# Channel_A.net
KiCad netlist of a schematic drawn in Altium Designer
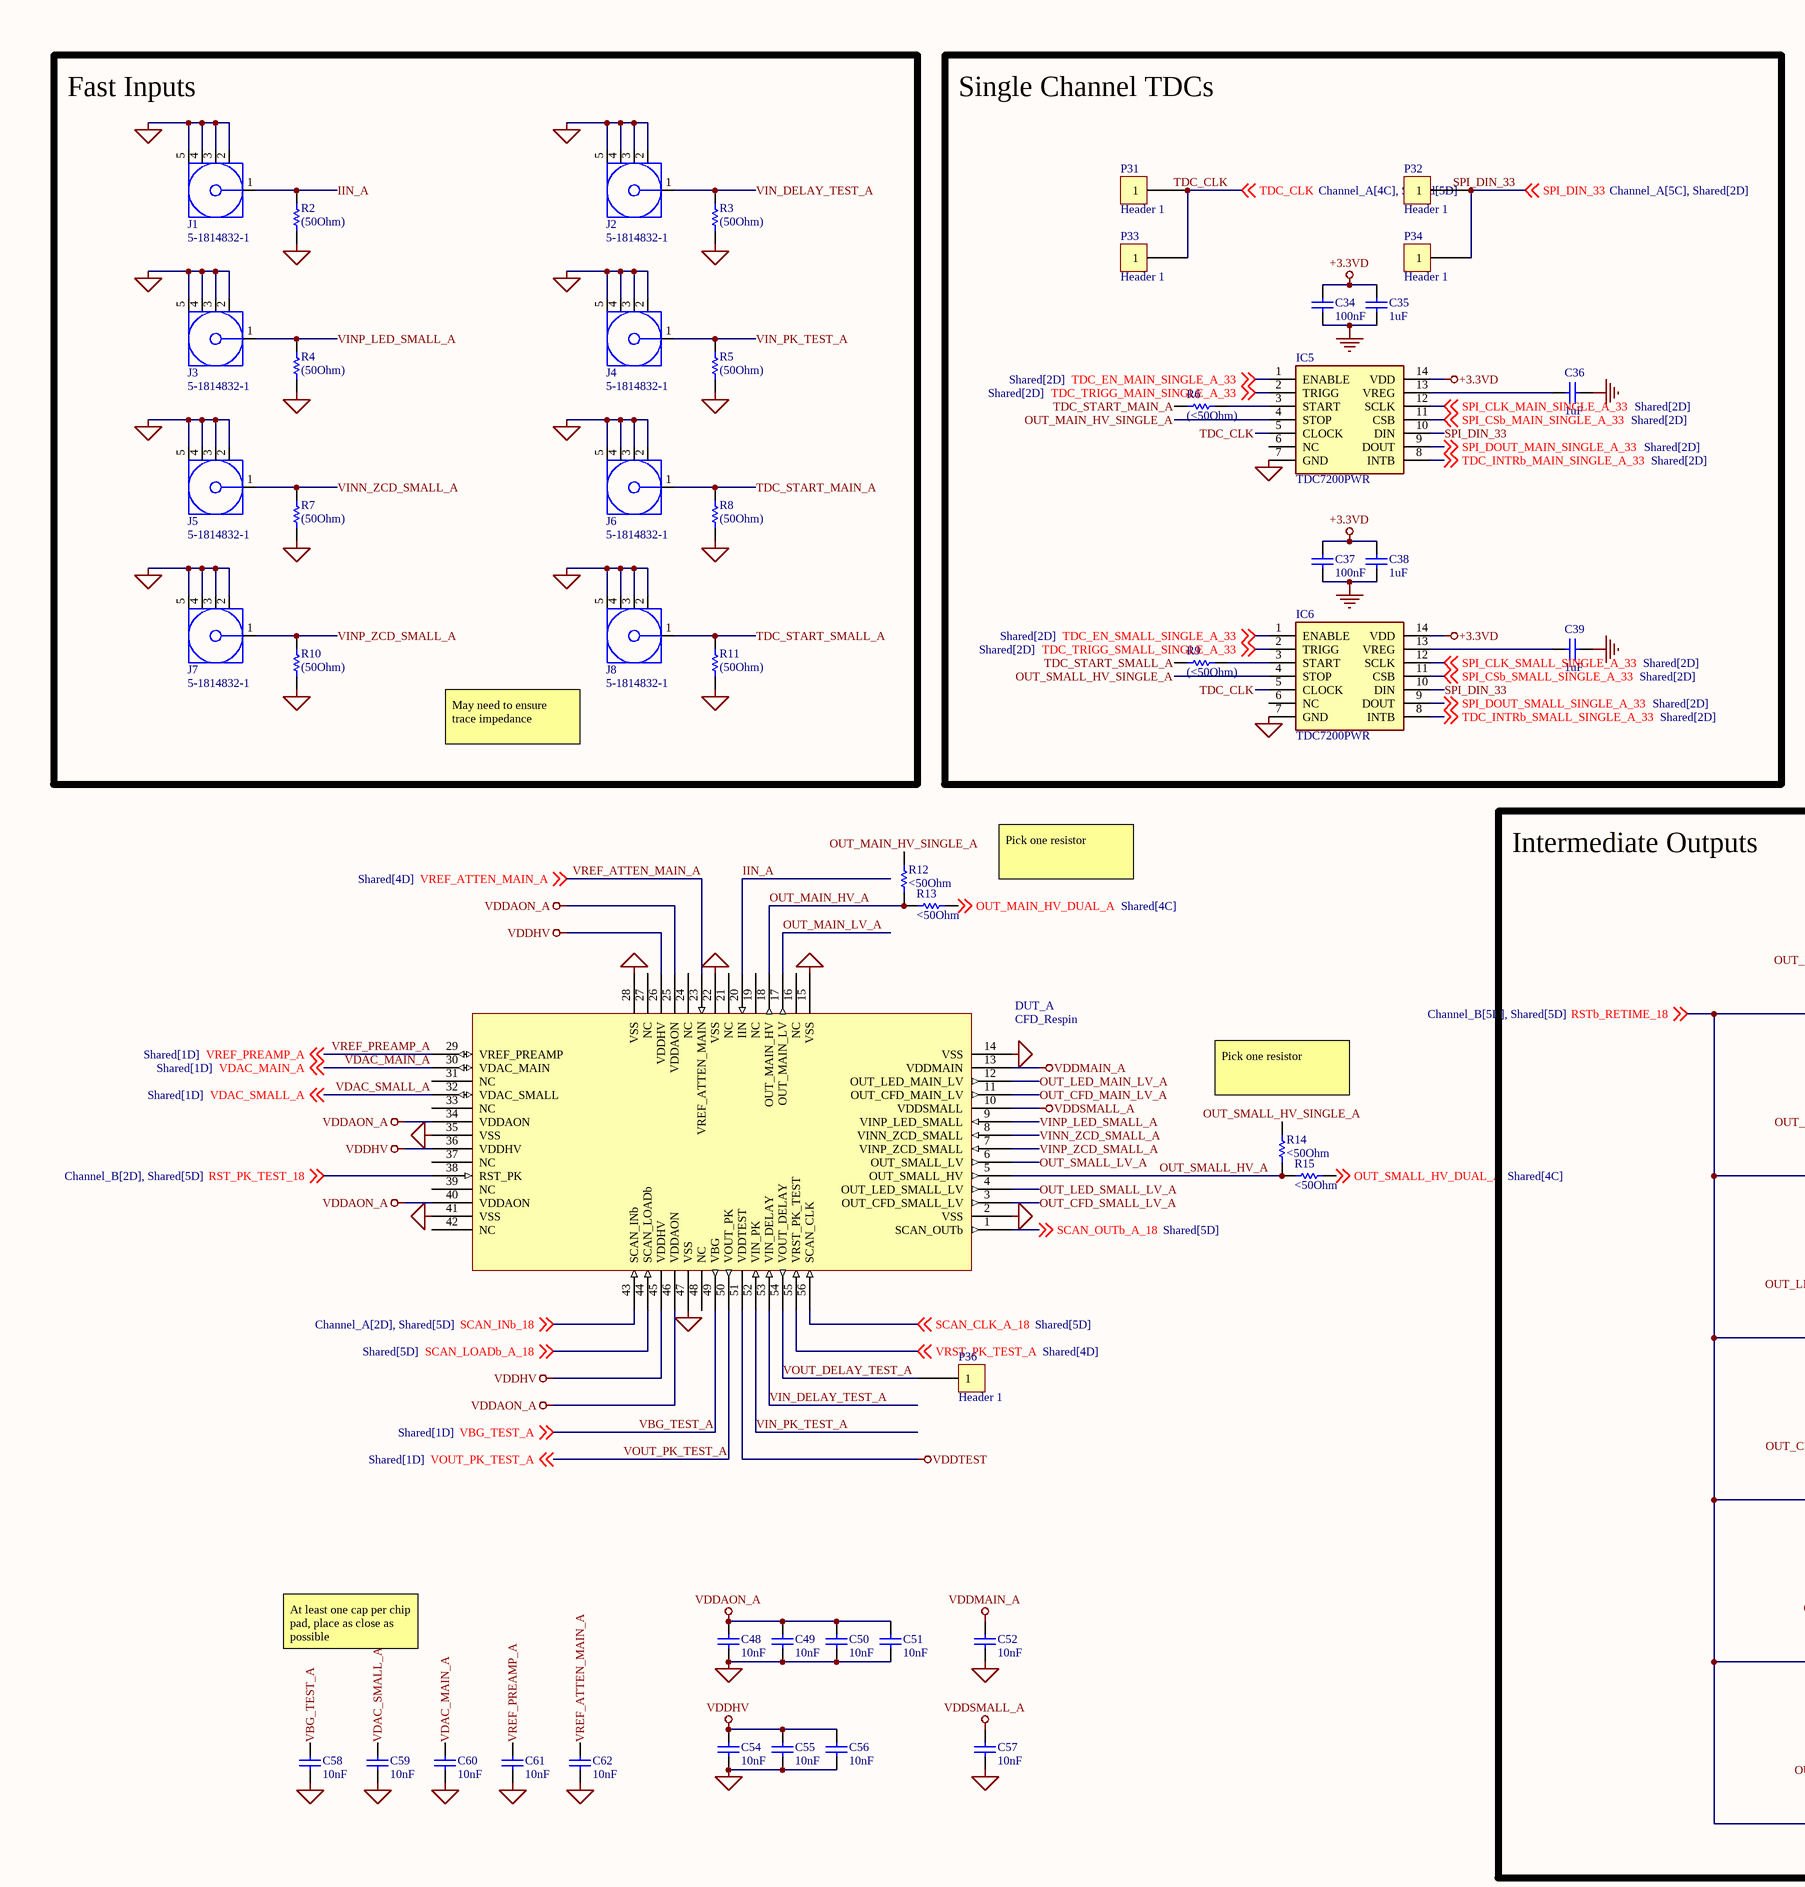
[diagram p0: Channel_A.SchDoc, left]
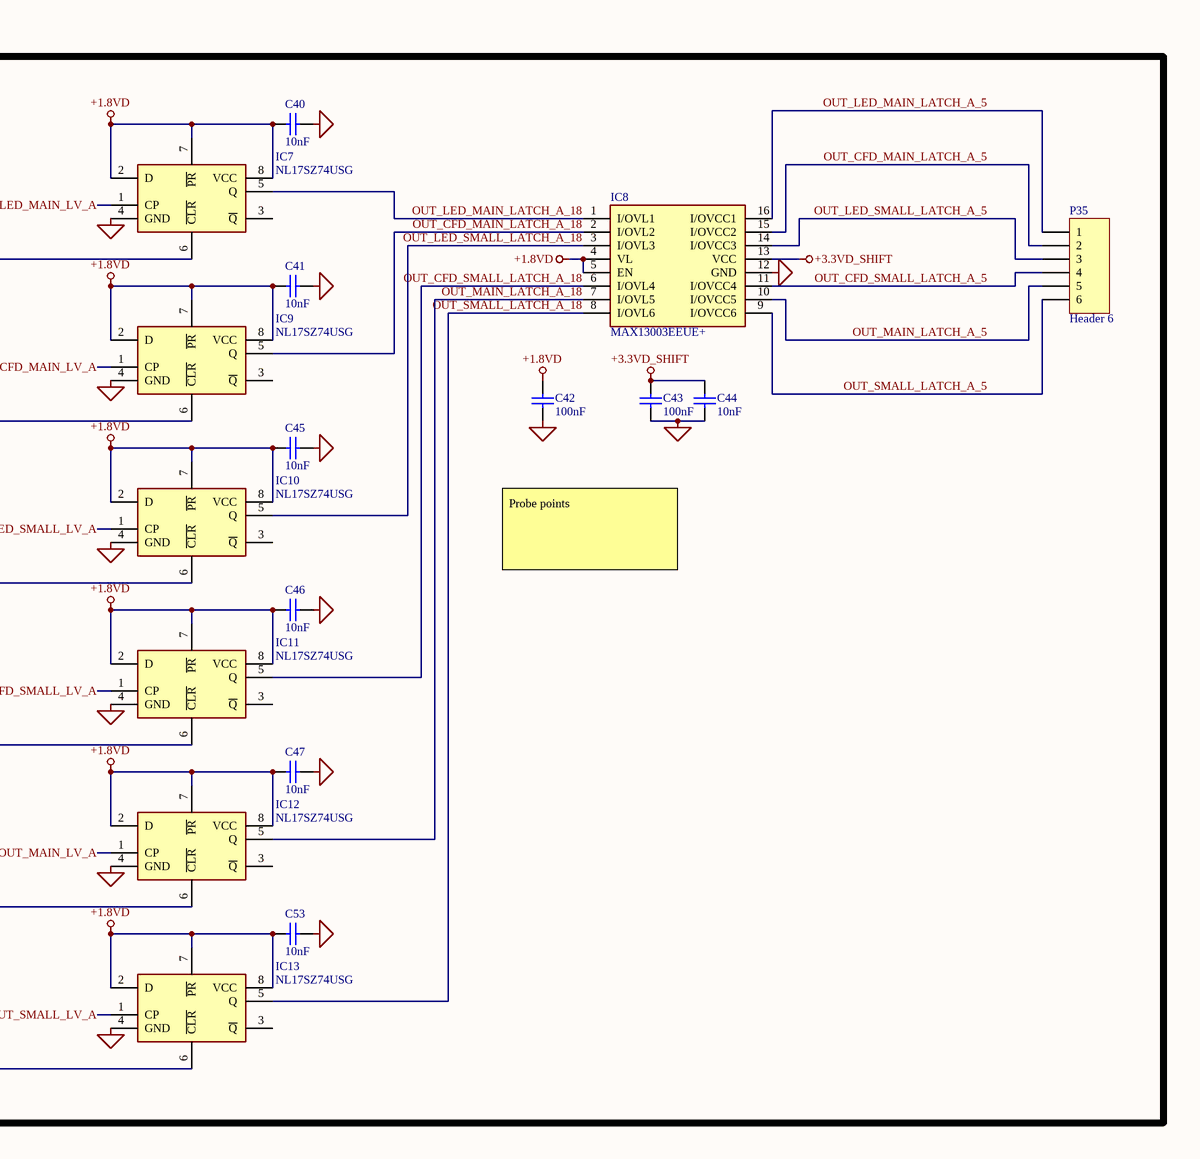
[diagram p1: Channel_A.SchDoc, right]

(export (version "E")
  (design (tool "Eeschema 10.0.6"))
  (components
    (comp (ref "C34")
      (value "100nF")
      (footprint "CAPC1608X90X35ML10T15")
      (description "0603")
      (fields (field (name "MANUFACTURER") "Murata"))
      (libsource (lib "Altium Content Vault") (part "CAP-NP-2"))
    )
    (comp (ref "C35")
      (value "1uF")
      (footprint "CAPC1608X90X35ML10T15")
      (description "0603")
      (fields (field (name "MANUFACTURER") "Murata"))
      (libsource (lib "Altium Content Vault") (part "CAP-NP-2"))
    )
    (comp (ref "C36")
      (value "1uF")
      (footprint "CAPC1608X90X35ML10T15")
      (description "0603")
      (fields (field (name "MANUFACTURER") "Murata"))
      (libsource (lib "Altium Content Vault") (part "CAP-NP-2"))
    )
    (comp (ref "C37")
      (value "100nF")
      (footprint "CAPC1608X90X35ML10T15")
      (description "0603")
      (fields (field (name "MANUFACTURER") "Murata"))
      (libsource (lib "Altium Content Vault") (part "CAP-NP-2"))
    )
    (comp (ref "C38")
      (value "1uF")
      (footprint "CAPC1608X90X35ML10T15")
      (description "0603")
      (fields (field (name "MANUFACTURER") "Murata"))
      (libsource (lib "Altium Content Vault") (part "CAP-NP-2"))
    )
    (comp (ref "C39")
      (value "1uF")
      (footprint "CAPC1608X90X35ML10T15")
      (description "0603")
      (fields (field (name "MANUFACTURER") "Murata"))
      (libsource (lib "Altium Content Vault") (part "CAP-NP-2"))
    )
    (comp (ref "C40")
      (value "10nF")
      (footprint "CAPC1608X90X35ML10T15")
      (description "0603")
      (fields (field (name "MANUFACTURER") "Murata"))
      (libsource (lib "Altium Content Vault") (part "CAP-NP-2"))
    )
    (comp (ref "C41")
      (value "10nF")
      (footprint "CAPC1608X90X35ML10T15")
      (description "0603")
      (fields (field (name "MANUFACTURER") "Murata"))
      (libsource (lib "Altium Content Vault") (part "CAP-NP-2"))
    )
    (comp (ref "C42")
      (value "100nF")
      (footprint "CAPC1608X90X35ML10T15")
      (description "0603")
      (fields (field (name "MANUFACTURER") "Murata"))
      (libsource (lib "Altium Content Vault") (part "CAP-NP-2"))
    )
    (comp (ref "C43")
      (value "100nF")
      (footprint "CAPC1608X90X35ML10T15")
      (description "0603")
      (fields (field (name "MANUFACTURER") "Murata"))
      (libsource (lib "Altium Content Vault") (part "CAP-NP-2"))
    )
    (comp (ref "C44")
      (value "10nF")
      (footprint "CAPC1608X90X35ML10T15")
      (description "0603")
      (fields (field (name "MANUFACTURER") "Murata"))
      (libsource (lib "Altium Content Vault") (part "CAP-NP-2"))
    )
    (comp (ref "C45")
      (value "10nF")
      (footprint "CAPC1608X90X35ML10T15")
      (description "0603")
      (fields (field (name "MANUFACTURER") "Murata"))
      (libsource (lib "Altium Content Vault") (part "CAP-NP-2"))
    )
    (comp (ref "C46")
      (value "10nF")
      (footprint "CAPC1608X90X35ML10T15")
      (description "0603")
      (fields (field (name "MANUFACTURER") "Murata"))
      (libsource (lib "Altium Content Vault") (part "CAP-NP-2"))
    )
    (comp (ref "C47")
      (value "10nF")
      (footprint "CAPC1608X90X35ML10T15")
      (description "0603")
      (fields (field (name "MANUFACTURER") "Murata"))
      (libsource (lib "Altium Content Vault") (part "CAP-NP-2"))
    )
    (comp (ref "C48")
      (value "10nF")
      (footprint "CAPC1608X90X35ML10T15")
      (description "0603")
      (fields (field (name "MANUFACTURER") "Murata"))
      (libsource (lib "Altium Content Vault") (part "CAP-NP-2"))
    )
    (comp (ref "C49")
      (value "10nF")
      (footprint "CAPC1608X90X35ML10T15")
      (description "0603")
      (fields (field (name "MANUFACTURER") "Murata"))
      (libsource (lib "Altium Content Vault") (part "CAP-NP-2"))
    )
    (comp (ref "C50")
      (value "10nF")
      (footprint "CAPC1608X90X35ML10T15")
      (description "0603")
      (fields (field (name "MANUFACTURER") "Murata"))
      (libsource (lib "Altium Content Vault") (part "CAP-NP-2"))
    )
    (comp (ref "C51")
      (value "10nF")
      (footprint "CAPC1608X90X35ML10T15")
      (description "0603")
      (fields (field (name "MANUFACTURER") "Murata"))
      (libsource (lib "Altium Content Vault") (part "CAP-NP-2"))
    )
    (comp (ref "C52")
      (value "10nF")
      (footprint "CAPC1608X90X35ML10T15")
      (description "0603")
      (fields (field (name "MANUFACTURER") "Murata"))
      (libsource (lib "Altium Content Vault") (part "CAP-NP-2"))
    )
    (comp (ref "C53")
      (value "10nF")
      (footprint "CAPC1608X90X35ML10T15")
      (description "0603")
      (fields (field (name "MANUFACTURER") "Murata"))
      (libsource (lib "Altium Content Vault") (part "CAP-NP-2"))
    )
    (comp (ref "C54")
      (value "10nF")
      (footprint "CAPC1608X90X35ML10T15")
      (description "0603")
      (fields (field (name "MANUFACTURER") "Murata"))
      (libsource (lib "Altium Content Vault") (part "CAP-NP-2"))
    )
    (comp (ref "C55")
      (value "10nF")
      (footprint "CAPC1608X90X35ML10T15")
      (description "0603")
      (fields (field (name "MANUFACTURER") "Murata"))
      (libsource (lib "Altium Content Vault") (part "CAP-NP-2"))
    )
    (comp (ref "C56")
      (value "10nF")
      (footprint "CAPC1608X90X35ML10T15")
      (description "0603")
      (fields (field (name "MANUFACTURER") "Murata"))
      (libsource (lib "Altium Content Vault") (part "CAP-NP-2"))
    )
    (comp (ref "C57")
      (value "10nF")
      (footprint "CAPC1608X90X35ML10T15")
      (description "0603")
      (fields (field (name "MANUFACTURER") "Murata"))
      (libsource (lib "Altium Content Vault") (part "CAP-NP-2"))
    )
    (comp (ref "C58")
      (value "10nF")
      (footprint "CAPC1608X90X35ML10T15")
      (description "0603")
      (fields (field (name "MANUFACTURER") "Murata"))
      (libsource (lib "Altium Content Vault") (part "CAP-NP-2"))
    )
    (comp (ref "C59")
      (value "10nF")
      (footprint "CAPC1608X90X35ML10T15")
      (description "0603")
      (fields (field (name "MANUFACTURER") "Murata"))
      (libsource (lib "Altium Content Vault") (part "CAP-NP-2"))
    )
    (comp (ref "C60")
      (value "10nF")
      (footprint "CAPC1608X90X35ML10T15")
      (description "0603")
      (fields (field (name "MANUFACTURER") "Murata"))
      (libsource (lib "Altium Content Vault") (part "CAP-NP-2"))
    )
    (comp (ref "C61")
      (value "10nF")
      (footprint "CAPC1608X90X35ML10T15")
      (description "0603")
      (fields (field (name "MANUFACTURER") "Murata"))
      (libsource (lib "Altium Content Vault") (part "CAP-NP-2"))
    )
    (comp (ref "C62")
      (value "10nF")
      (footprint "CAPC1608X90X35ML10T15")
      (description "0603")
      (fields (field (name "MANUFACTURER") "Murata"))
      (libsource (lib "Altium Content Vault") (part "CAP-NP-2"))
    )
    (comp (ref "DUT_A")
      (value "CFD_Respin")
      (footprint "QFN50P800X800X80_HS-57N_WIDEVIAS")
      (libsource (lib "intlib") (part "CFD_Respin"))
    )
    (comp (ref "IC5")
      (value "TDC7200PWR")
      (footprint "SamacSys:SOP65P640X120-14N")
      (description "Integrated Circuit")
      (libsource (lib "*") (part "TDC7200PWR"))
    )
    (comp (ref "IC6")
      (value "TDC7200PWR")
      (footprint "SamacSys:SOP65P640X120-14N")
      (description "Integrated Circuit")
      (libsource (lib "*") (part "TDC7200PWR"))
    )
    (comp (ref "IC7")
      (value "NL17SZ74USG")
      (footprint "SamacSys:SOP50P310X90-8N")
      (description "Flip Flops 1.65-5.5V CMOS Single D-Type")
      (libsource (lib "SamacSys") (part "NL17SZ74USG"))
    )
    (comp (ref "IC8")
      (value "MAX13003EEUE+")
      (footprint "SamacSys:SOP65P640X110-16N")
      (description "Integrated Circuit")
      (libsource (lib "*") (part "MAX13003EEUE+"))
    )
    (comp (ref "IC9")
      (value "NL17SZ74USG")
      (footprint "SamacSys:SOP50P310X90-8N")
      (description "Flip Flops 1.65-5.5V CMOS Single D-Type")
      (libsource (lib "SamacSys") (part "NL17SZ74USG"))
    )
    (comp (ref "IC10")
      (value "NL17SZ74USG")
      (footprint "SamacSys:SOP50P310X90-8N")
      (description "Flip Flops 1.65-5.5V CMOS Single D-Type")
      (libsource (lib "SamacSys") (part "NL17SZ74USG"))
    )
    (comp (ref "IC11")
      (value "NL17SZ74USG")
      (footprint "SamacSys:SOP50P310X90-8N")
      (description "Flip Flops 1.65-5.5V CMOS Single D-Type")
      (libsource (lib "SamacSys") (part "NL17SZ74USG"))
    )
    (comp (ref "IC12")
      (value "NL17SZ74USG")
      (footprint "SamacSys:SOP50P310X90-8N")
      (description "Flip Flops 1.65-5.5V CMOS Single D-Type")
      (libsource (lib "SamacSys") (part "NL17SZ74USG"))
    )
    (comp (ref "IC13")
      (value "NL17SZ74USG")
      (footprint "SamacSys:SOP50P310X90-8N")
      (description "Flip Flops 1.65-5.5V CMOS Single D-Type")
      (libsource (lib "SamacSys") (part "NL17SZ74USG"))
    )
    (comp (ref "J1")
      (value "5-1814832-1")
      (footprint "TECO-5-1814832-1_V")
      (fields (field (name "MANUFACTURER") "TE Connectivity"))
      (libsource (lib "Altium Content Vault") (part "CN-S-4F-RF5"))
    )
    (comp (ref "J2")
      (value "5-1814832-1")
      (footprint "TECO-5-1814832-1_V")
      (fields (field (name "MANUFACTURER") "TE Connectivity"))
      (libsource (lib "Altium Content Vault") (part "CN-S-4F-RF5"))
    )
    (comp (ref "J3")
      (value "5-1814832-1")
      (footprint "TECO-5-1814832-1_V")
      (fields (field (name "MANUFACTURER") "TE Connectivity"))
      (libsource (lib "Altium Content Vault") (part "CN-S-4F-RF5"))
    )
    (comp (ref "J4")
      (value "5-1814832-1")
      (footprint "TECO-5-1814832-1_V")
      (fields (field (name "MANUFACTURER") "TE Connectivity"))
      (libsource (lib "Altium Content Vault") (part "CN-S-4F-RF5"))
    )
    (comp (ref "J5")
      (value "5-1814832-1")
      (footprint "TECO-5-1814832-1_V")
      (fields (field (name "MANUFACTURER") "TE Connectivity"))
      (libsource (lib "Altium Content Vault") (part "CN-S-4F-RF5"))
    )
    (comp (ref "J6")
      (value "5-1814832-1")
      (footprint "TECO-5-1814832-1_V")
      (fields (field (name "MANUFACTURER") "TE Connectivity"))
      (libsource (lib "Altium Content Vault") (part "CN-S-4F-RF5"))
    )
    (comp (ref "J7")
      (value "5-1814832-1")
      (footprint "TECO-5-1814832-1_V")
      (fields (field (name "MANUFACTURER") "TE Connectivity"))
      (libsource (lib "Altium Content Vault") (part "CN-S-4F-RF5"))
    )
    (comp (ref "J8")
      (value "5-1814832-1")
      (footprint "TECO-5-1814832-1_V")
      (fields (field (name "MANUFACTURER") "TE Connectivity"))
      (libsource (lib "Altium Content Vault") (part "CN-S-4F-RF5"))
    )
    (comp (ref "P31") (value "Header 1") (footprint "Header1") (libsource (lib "intlib") (part "Header 1")))
    (comp (ref "P32") (value "Header 1") (footprint "Header1") (libsource (lib "intlib") (part "Header 1")))
    (comp (ref "P33") (value "Header 1") (footprint "Header1") (libsource (lib "intlib") (part "Header 1")))
    (comp (ref "P34") (value "Header 1") (footprint "Header1") (libsource (lib "intlib") (part "Header 1")))
    (comp (ref "P35")
      (value "Header 6")
      (footprint "HDR1X6")
      (description "Header, 6-Pin")
      (fields (field (name "PUBLISHER") "Altium Limited"))
      (libsource (lib "Miscellaneous Connectors") (part "Header 6"))
    )
    (comp (ref "P36") (value "Header 1") (footprint "Header1") (libsource (lib "") (part "Header 1_1")))
    (comp (ref "R2")
      (value "(50Ohm)")
      (footprint "RESC1609X50X30NL8T20")
      (description "0603")
      (fields (field (name "MANUFACTURER") "Vishay Semiconductor"))
      (libsource (lib "Altium Content Vault") (part "RES-2"))
    )
    (comp (ref "R3")
      (value "(50Ohm)")
      (footprint "RESC1609X50X30NL8T20")
      (description "0603")
      (fields (field (name "MANUFACTURER") "Vishay Semiconductor"))
      (libsource (lib "Altium Content Vault") (part "RES-2"))
    )
    (comp (ref "R4")
      (value "(50Ohm)")
      (footprint "RESC1609X50X30NL8T20")
      (description "0603")
      (fields (field (name "MANUFACTURER") "Vishay Semiconductor"))
      (libsource (lib "Altium Content Vault") (part "RES-2"))
    )
    (comp (ref "R5")
      (value "(50Ohm)")
      (footprint "RESC1609X50X30NL8T20")
      (description "0603")
      (fields (field (name "MANUFACTURER") "Vishay Semiconductor"))
      (libsource (lib "Altium Content Vault") (part "RES-2"))
    )
    (comp (ref "R6")
      (value "(<50Ohm)")
      (footprint "RESC1609X50X30NL8T20")
      (description "0603")
      (fields (field (name "MANUFACTURER") "Vishay Semiconductor"))
      (libsource (lib "Altium Content Vault") (part "RES-2"))
    )
    (comp (ref "R7")
      (value "(50Ohm)")
      (footprint "RESC1609X50X30NL8T20")
      (description "0603")
      (fields (field (name "MANUFACTURER") "Vishay Semiconductor"))
      (libsource (lib "Altium Content Vault") (part "RES-2"))
    )
    (comp (ref "R8")
      (value "(50Ohm)")
      (footprint "RESC1609X50X30NL8T20")
      (description "0603")
      (fields (field (name "MANUFACTURER") "Vishay Semiconductor"))
      (libsource (lib "Altium Content Vault") (part "RES-2"))
    )
    (comp (ref "R9")
      (value "(<50Ohm)")
      (footprint "RESC1609X50X30NL8T20")
      (description "0603")
      (fields (field (name "MANUFACTURER") "Vishay Semiconductor"))
      (libsource (lib "Altium Content Vault") (part "RES-2"))
    )
    (comp (ref "R10")
      (value "(50Ohm)")
      (footprint "RESC1609X50X30NL8T20")
      (description "0603")
      (fields (field (name "MANUFACTURER") "Vishay Semiconductor"))
      (libsource (lib "Altium Content Vault") (part "RES-2"))
    )
    (comp (ref "R11")
      (value "(50Ohm)")
      (footprint "RESC1609X50X30NL8T20")
      (description "0603")
      (fields (field (name "MANUFACTURER") "Vishay Semiconductor"))
      (libsource (lib "Altium Content Vault") (part "RES-2"))
    )
    (comp (ref "R12")
      (value "<50Ohm")
      (footprint "RESC1609X50X30NL8T20")
      (description "0603")
      (fields (field (name "MANUFACTURER") "Vishay Semiconductor"))
      (libsource (lib "Altium Content Vault") (part "RES-2"))
    )
    (comp (ref "R13")
      (value "<50Ohm")
      (footprint "RESC1609X50X30NL8T20")
      (description "0603")
      (fields (field (name "MANUFACTURER") "Vishay Semiconductor"))
      (libsource (lib "Altium Content Vault") (part "RES-2"))
    )
    (comp (ref "R14")
      (value "<50Ohm")
      (footprint "RESC1609X50X30NL8T20")
      (description "0603")
      (fields (field (name "MANUFACTURER") "Vishay Semiconductor"))
      (libsource (lib "Altium Content Vault") (part "RES-2"))
    )
    (comp (ref "R15")
      (value "<50Ohm")
      (footprint "RESC1609X50X30NL8T20")
      (description "0603")
      (fields (field (name "MANUFACTURER") "Vishay Semiconductor"))
      (libsource (lib "Altium Content Vault") (part "RES-2"))
    )
  )
  (nets
    (net (code "1") (name "+1.8VD") (class "Default")
      (node (ref "C40") (pin "2") (pinfunction "2_2") (pintype "passive"))
      (node (ref "C41") (pin "2") (pinfunction "2_2") (pintype "passive"))
      (node (ref "C42") (pin "2") (pinfunction "2_2") (pintype "passive"))
      (node (ref "C45") (pin "2") (pinfunction "2_2") (pintype "passive"))
      (node (ref "C46") (pin "2") (pinfunction "2_2") (pintype "passive"))
      (node (ref "C47") (pin "2") (pinfunction "2_2") (pintype "passive"))
      (node (ref "C53") (pin "2") (pinfunction "2_2") (pintype "passive"))
      (node (ref "IC10") (pin "2") (pinfunction "D_2") (pintype "passive"))
      (node (ref "IC10") (pin "7") (pinfunction "~{PR}_7") (pintype "passive"))
      (node (ref "IC10") (pin "8") (pinfunction "VCC_8") (pintype "passive"))
      (node (ref "IC11") (pin "2") (pinfunction "D_2") (pintype "passive"))
      (node (ref "IC11") (pin "7") (pinfunction "~{PR}_7") (pintype "passive"))
      (node (ref "IC11") (pin "8") (pinfunction "VCC_8") (pintype "passive"))
      (node (ref "IC12") (pin "2") (pinfunction "D_2") (pintype "passive"))
      (node (ref "IC12") (pin "7") (pinfunction "~{PR}_7") (pintype "passive"))
      (node (ref "IC12") (pin "8") (pinfunction "VCC_8") (pintype "passive"))
      (node (ref "IC13") (pin "2") (pinfunction "D_2") (pintype "passive"))
      (node (ref "IC13") (pin "7") (pinfunction "~{PR}_7") (pintype "passive"))
      (node (ref "IC13") (pin "8") (pinfunction "VCC_8") (pintype "passive"))
      (node (ref "IC7") (pin "2") (pinfunction "D_2") (pintype "passive"))
      (node (ref "IC7") (pin "7") (pinfunction "~{PR}_7") (pintype "passive"))
      (node (ref "IC7") (pin "8") (pinfunction "VCC_8") (pintype "passive"))
      (node (ref "IC8") (pin "4") (pinfunction "VL_4") (pintype "passive"))
      (node (ref "IC8") (pin "5") (pinfunction "EN_5") (pintype "passive"))
      (node (ref "IC9") (pin "2") (pinfunction "D_2") (pintype "passive"))
      (node (ref "IC9") (pin "7") (pinfunction "~{PR}_7") (pintype "passive"))
      (node (ref "IC9") (pin "8") (pinfunction "VCC_8") (pintype "passive"))
    )
    (net (code "2") (name "+3.3VD") (class "Default")
      (node (ref "C34") (pin "1") (pinfunction "1_1") (pintype "passive"))
      (node (ref "C35") (pin "1") (pinfunction "1_1") (pintype "passive"))
      (node (ref "C37") (pin "1") (pinfunction "1_1") (pintype "passive"))
      (node (ref "C38") (pin "1") (pinfunction "1_1") (pintype "passive"))
      (node (ref "IC5") (pin "14") (pinfunction "VDD_14") (pintype "passive"))
      (node (ref "IC6") (pin "14") (pinfunction "VDD_14") (pintype "passive"))
    )
    (net (code "3") (name "+3.3VD_SHIFT") (class "Default")
      (node (ref "C43") (pin "2") (pinfunction "2_2") (pintype "passive"))
      (node (ref "C44") (pin "2") (pinfunction "2_2") (pintype "passive"))
      (node (ref "IC8") (pin "13") (pinfunction "VCC_13") (pintype "passive"))
    )
    (net (code "4") (name "/IIN_A") (class "Default")
      (node (ref "DUT_A") (pin "20") (pinfunction "IIN_20") (pintype "input"))
      (node (ref "J1") (pin "1") (pinfunction "1_1") (pintype "passive"))
      (node (ref "R2") (pin "2") (pinfunction "2_2") (pintype "passive"))
    )
    (net (code "5") (name "/OUT_CFD_MAIN_LATCH_A_5") (class "Default")
      (node (ref "IC8") (pin "15") (pinfunction "I/OVCC2_15") (pintype "passive"))
      (node (ref "P35") (pin "2") (pinfunction "2_2") (pintype "passive"))
    )
    (net (code "6") (name "/OUT_CFD_MAIN_LATCH_A_18") (class "Default")
      (node (ref "IC8") (pin "2") (pinfunction "I/OVL2_2") (pintype "passive"))
      (node (ref "IC9") (pin "5") (pinfunction "Q_5") (pintype "passive"))
    )
    (net (code "7") (name "/OUT_CFD_MAIN_LV_A") (class "Default")
      (node (ref "DUT_A") (pin "11") (pinfunction "OUT_CFD_MAIN_LV_11") (pintype "output"))
      (node (ref "IC9") (pin "1") (pinfunction "CP_1") (pintype "passive"))
    )
    (net (code "8") (name "/OUT_CFD_SMALL_LATCH_A_5") (class "Default")
      (node (ref "IC8") (pin "11") (pinfunction "I/OVCC4_11") (pintype "passive"))
      (node (ref "P35") (pin "4") (pinfunction "4_4") (pintype "passive"))
    )
    (net (code "9") (name "/OUT_CFD_SMALL_LATCH_A_18") (class "Default")
      (node (ref "IC11") (pin "5") (pinfunction "Q_5") (pintype "passive"))
      (node (ref "IC8") (pin "6") (pinfunction "I/OVL4_6") (pintype "passive"))
    )
    (net (code "10") (name "/OUT_CFD_SMALL_LV_A") (class "Default")
      (node (ref "DUT_A") (pin "3") (pinfunction "OUT_CFD_SMALL_LV_3") (pintype "output"))
      (node (ref "IC11") (pin "1") (pinfunction "CP_1") (pintype "passive"))
    )
    (net (code "11") (name "/OUT_LED_MAIN_LATCH_A_5") (class "Default")
      (node (ref "IC8") (pin "16") (pinfunction "I/OVCC1_16") (pintype "passive"))
      (node (ref "P35") (pin "1") (pinfunction "1_1") (pintype "passive"))
    )
    (net (code "12") (name "/OUT_LED_MAIN_LATCH_A_18") (class "Default")
      (node (ref "IC7") (pin "5") (pinfunction "Q_5") (pintype "passive"))
      (node (ref "IC8") (pin "1") (pinfunction "I/OVL1_1") (pintype "passive"))
    )
    (net (code "13") (name "/OUT_LED_MAIN_LV_A") (class "Default")
      (node (ref "DUT_A") (pin "12") (pinfunction "OUT_LED_MAIN_LV_12") (pintype "output"))
      (node (ref "IC7") (pin "1") (pinfunction "CP_1") (pintype "passive"))
    )
    (net (code "14") (name "/OUT_LED_SMALL_LATCH_A_5") (class "Default")
      (node (ref "IC8") (pin "14") (pinfunction "I/OVCC3_14") (pintype "passive"))
      (node (ref "P35") (pin "3") (pinfunction "3_3") (pintype "passive"))
    )
    (net (code "15") (name "/OUT_LED_SMALL_LATCH_A_18") (class "Default")
      (node (ref "IC10") (pin "5") (pinfunction "Q_5") (pintype "passive"))
      (node (ref "IC8") (pin "3") (pinfunction "I/OVL3_3") (pintype "passive"))
    )
    (net (code "16") (name "/OUT_LED_SMALL_LV_A") (class "Default")
      (node (ref "DUT_A") (pin "4") (pinfunction "OUT_LED_SMALL_LV_4") (pintype "output"))
      (node (ref "IC10") (pin "1") (pinfunction "CP_1") (pintype "passive"))
    )
    (net (code "17") (name "/OUT_MAIN_HV_A") (class "Default")
      (node (ref "DUT_A") (pin "18") (pinfunction "OUT_MAIN_HV_18") (pintype "output"))
      (node (ref "R12") (pin "2") (pinfunction "2_2") (pintype "passive"))
      (node (ref "R13") (pin "1") (pinfunction "1_1") (pintype "passive"))
    )
    (net (code "18") (name "/OUT_MAIN_HV_SINGLE_A") (class "Default")
      (node (ref "IC5") (pin "4") (pinfunction "STOP_4") (pintype "passive"))
      (node (ref "R12") (pin "1") (pinfunction "1_1") (pintype "passive"))
    )
    (net (code "19") (name "/OUT_MAIN_LATCH_A_5") (class "Default")
      (node (ref "IC8") (pin "10") (pinfunction "I/OVCC5_10") (pintype "passive"))
      (node (ref "P35") (pin "5") (pinfunction "5_5") (pintype "passive"))
    )
    (net (code "20") (name "/OUT_MAIN_LATCH_A_18") (class "Default")
      (node (ref "IC12") (pin "5") (pinfunction "Q_5") (pintype "passive"))
      (node (ref "IC8") (pin "7") (pinfunction "I/OVL5_7") (pintype "passive"))
    )
    (net (code "21") (name "/OUT_MAIN_LV_A") (class "Default")
      (node (ref "DUT_A") (pin "17") (pinfunction "OUT_MAIN_LV_17") (pintype "output"))
      (node (ref "IC12") (pin "1") (pinfunction "CP_1") (pintype "passive"))
    )
    (net (code "22") (name "/OUT_SMALL_HV_A") (class "Default")
      (node (ref "DUT_A") (pin "5") (pinfunction "OUT_SMALL_HV_5") (pintype "output"))
      (node (ref "R14") (pin "2") (pinfunction "2_2") (pintype "passive"))
      (node (ref "R15") (pin "1") (pinfunction "1_1") (pintype "passive"))
    )
    (net (code "23") (name "/OUT_SMALL_HV_SINGLE_A") (class "Default")
      (node (ref "IC6") (pin "4") (pinfunction "STOP_4") (pintype "passive"))
      (node (ref "R14") (pin "1") (pinfunction "1_1") (pintype "passive"))
    )
    (net (code "24") (name "/OUT_SMALL_LATCH_A_5") (class "Default")
      (node (ref "IC8") (pin "9") (pinfunction "I/OVCC6_9") (pintype "passive"))
      (node (ref "P35") (pin "6") (pinfunction "6_6") (pintype "passive"))
    )
    (net (code "25") (name "/OUT_SMALL_LATCH_A_18") (class "Default")
      (node (ref "IC13") (pin "5") (pinfunction "Q_5") (pintype "passive"))
      (node (ref "IC8") (pin "8") (pinfunction "I/OVL6_8") (pintype "passive"))
    )
    (net (code "26") (name "/OUT_SMALL_LV_A") (class "Default")
      (node (ref "DUT_A") (pin "6") (pinfunction "OUT_SMALL_LV_6") (pintype "output"))
      (node (ref "IC13") (pin "1") (pinfunction "CP_1") (pintype "passive"))
    )
    (net (code "27") (name "/TDC_START_MAIN_A") (class "Default")
      (node (ref "J6") (pin "1") (pinfunction "1_1") (pintype "passive"))
      (node (ref "R6") (pin "1") (pinfunction "1_1") (pintype "passive"))
      (node (ref "R8") (pin "2") (pinfunction "2_2") (pintype "passive"))
    )
    (net (code "28") (name "/TDC_START_SMALL_A") (class "Default")
      (node (ref "J8") (pin "1") (pinfunction "1_1") (pintype "passive"))
      (node (ref "R11") (pin "2") (pinfunction "2_2") (pintype "passive"))
      (node (ref "R9") (pin "1") (pinfunction "1_1") (pintype "passive"))
    )
    (net (code "29") (name "/VINN_ZCD_SMALL_A") (class "Default")
      (node (ref "DUT_A") (pin "8") (pinfunction "VINN_ZCD_SMALL_8") (pintype "input"))
      (node (ref "J5") (pin "1") (pinfunction "1_1") (pintype "passive"))
      (node (ref "R7") (pin "2") (pinfunction "2_2") (pintype "passive"))
    )
    (net (code "30") (name "/VINP_LED_SMALL_A") (class "Default")
      (node (ref "DUT_A") (pin "9") (pinfunction "VINP_LED_SMALL_9") (pintype "input"))
      (node (ref "J3") (pin "1") (pinfunction "1_1") (pintype "passive"))
      (node (ref "R4") (pin "2") (pinfunction "2_2") (pintype "passive"))
    )
    (net (code "31") (name "/VINP_ZCD_SMALL_A") (class "Default")
      (node (ref "DUT_A") (pin "7") (pinfunction "VINP_ZCD_SMALL_7") (pintype "input"))
      (node (ref "J7") (pin "1") (pinfunction "1_1") (pintype "passive"))
      (node (ref "R10") (pin "2") (pinfunction "2_2") (pintype "passive"))
    )
    (net (code "32") (name "/VIN_DELAY_TEST_A") (class "Default")
      (node (ref "DUT_A") (pin "53") (pinfunction "VIN_DELAY_53") (pintype "input"))
      (node (ref "J2") (pin "1") (pinfunction "1_1") (pintype "passive"))
      (node (ref "R3") (pin "2") (pinfunction "2_2") (pintype "passive"))
    )
    (net (code "33") (name "/VIN_PK_TEST_A") (class "Default")
      (node (ref "DUT_A") (pin "52") (pinfunction "VIN_PK_52") (pintype "input"))
      (node (ref "J4") (pin "1") (pinfunction "1_1") (pintype "passive"))
      (node (ref "R5") (pin "2") (pinfunction "2_2") (pintype "passive"))
    )
    (net (code "34") (name "/VOUT_DELAY_TEST_A") (class "Default")
      (node (ref "DUT_A") (pin "54") (pinfunction "VOUT_DELAY_54") (pintype "output"))
      (node (ref "P36") (pin "1") (pinfunction "1_1") (pintype "passive"))
    )
    (net (code "35") (name "GND") (class "Default")
      (node (ref "C34") (pin "2") (pinfunction "2_2") (pintype "passive"))
      (node (ref "C35") (pin "2") (pinfunction "2_2") (pintype "passive"))
      (node (ref "C36") (pin "2") (pinfunction "2_2") (pintype "passive"))
      (node (ref "C37") (pin "2") (pinfunction "2_2") (pintype "passive"))
      (node (ref "C38") (pin "2") (pinfunction "2_2") (pintype "passive"))
      (node (ref "C39") (pin "2") (pinfunction "2_2") (pintype "passive"))
      (node (ref "C40") (pin "1") (pinfunction "1_1") (pintype "passive"))
      (node (ref "C41") (pin "1") (pinfunction "1_1") (pintype "passive"))
      (node (ref "C42") (pin "1") (pinfunction "1_1") (pintype "passive"))
      (node (ref "C43") (pin "1") (pinfunction "1_1") (pintype "passive"))
      (node (ref "C44") (pin "1") (pinfunction "1_1") (pintype "passive"))
      (node (ref "C45") (pin "1") (pinfunction "1_1") (pintype "passive"))
      (node (ref "C46") (pin "1") (pinfunction "1_1") (pintype "passive"))
      (node (ref "C47") (pin "1") (pinfunction "1_1") (pintype "passive"))
      (node (ref "C48") (pin "1") (pinfunction "1_1") (pintype "passive"))
      (node (ref "C49") (pin "1") (pinfunction "1_1") (pintype "passive"))
      (node (ref "C50") (pin "1") (pinfunction "1_1") (pintype "passive"))
      (node (ref "C51") (pin "1") (pinfunction "1_1") (pintype "passive"))
      (node (ref "C52") (pin "1") (pinfunction "1_1") (pintype "passive"))
      (node (ref "C53") (pin "1") (pinfunction "1_1") (pintype "passive"))
      (node (ref "C54") (pin "1") (pinfunction "1_1") (pintype "passive"))
      (node (ref "C55") (pin "1") (pinfunction "1_1") (pintype "passive"))
      (node (ref "C56") (pin "1") (pinfunction "1_1") (pintype "passive"))
      (node (ref "C57") (pin "1") (pinfunction "1_1") (pintype "passive"))
      (node (ref "C58") (pin "1") (pinfunction "1_1") (pintype "passive"))
      (node (ref "C59") (pin "1") (pinfunction "1_1") (pintype "passive"))
      (node (ref "C60") (pin "1") (pinfunction "1_1") (pintype "passive"))
      (node (ref "C61") (pin "1") (pinfunction "1_1") (pintype "passive"))
      (node (ref "C62") (pin "1") (pinfunction "1_1") (pintype "passive"))
      (node (ref "DUT_A") (pin "14") (pinfunction "VSS_14") (pintype "power_in"))
      (node (ref "DUT_A") (pin "15") (pinfunction "VSS_15") (pintype "power_in"))
      (node (ref "DUT_A") (pin "2") (pinfunction "VSS_2") (pintype "power_in"))
      (node (ref "DUT_A") (pin "22") (pinfunction "VSS_22") (pintype "power_in"))
      (node (ref "DUT_A") (pin "28") (pinfunction "VSS_28") (pintype "power_in"))
      (node (ref "DUT_A") (pin "35") (pinfunction "VSS_35") (pintype "power_in"))
      (node (ref "DUT_A") (pin "41") (pinfunction "VSS_41") (pintype "power_in"))
      (node (ref "DUT_A") (pin "47") (pinfunction "VSS_47") (pintype "power_in"))
      (node (ref "IC10") (pin "4") (pinfunction "GND_4") (pintype "passive"))
      (node (ref "IC11") (pin "4") (pinfunction "GND_4") (pintype "passive"))
      (node (ref "IC12") (pin "4") (pinfunction "GND_4") (pintype "passive"))
      (node (ref "IC13") (pin "4") (pinfunction "GND_4") (pintype "passive"))
      (node (ref "IC5") (pin "7") (pinfunction "GND_7") (pintype "passive"))
      (node (ref "IC6") (pin "7") (pinfunction "GND_7") (pintype "passive"))
      (node (ref "IC7") (pin "4") (pinfunction "GND_4") (pintype "passive"))
      (node (ref "IC8") (pin "12") (pinfunction "GND_12") (pintype "passive"))
      (node (ref "IC9") (pin "4") (pinfunction "GND_4") (pintype "passive"))
      (node (ref "J1") (pin "2") (pinfunction "2_2") (pintype "passive"))
      (node (ref "J1") (pin "3") (pinfunction "3_3") (pintype "passive"))
      (node (ref "J1") (pin "4") (pinfunction "4_4") (pintype "passive"))
      (node (ref "J1") (pin "5") (pinfunction "5_5") (pintype "passive"))
      (node (ref "J2") (pin "2") (pinfunction "2_2") (pintype "passive"))
      (node (ref "J2") (pin "3") (pinfunction "3_3") (pintype "passive"))
      (node (ref "J2") (pin "4") (pinfunction "4_4") (pintype "passive"))
      (node (ref "J2") (pin "5") (pinfunction "5_5") (pintype "passive"))
      (node (ref "J3") (pin "2") (pinfunction "2_2") (pintype "passive"))
      (node (ref "J3") (pin "3") (pinfunction "3_3") (pintype "passive"))
      (node (ref "J3") (pin "4") (pinfunction "4_4") (pintype "passive"))
      (node (ref "J3") (pin "5") (pinfunction "5_5") (pintype "passive"))
      (node (ref "J4") (pin "2") (pinfunction "2_2") (pintype "passive"))
      (node (ref "J4") (pin "3") (pinfunction "3_3") (pintype "passive"))
      (node (ref "J4") (pin "4") (pinfunction "4_4") (pintype "passive"))
      (node (ref "J4") (pin "5") (pinfunction "5_5") (pintype "passive"))
      (node (ref "J5") (pin "2") (pinfunction "2_2") (pintype "passive"))
      (node (ref "J5") (pin "3") (pinfunction "3_3") (pintype "passive"))
      (node (ref "J5") (pin "4") (pinfunction "4_4") (pintype "passive"))
      (node (ref "J5") (pin "5") (pinfunction "5_5") (pintype "passive"))
      (node (ref "J6") (pin "2") (pinfunction "2_2") (pintype "passive"))
      (node (ref "J6") (pin "3") (pinfunction "3_3") (pintype "passive"))
      (node (ref "J6") (pin "4") (pinfunction "4_4") (pintype "passive"))
      (node (ref "J6") (pin "5") (pinfunction "5_5") (pintype "passive"))
      (node (ref "J7") (pin "2") (pinfunction "2_2") (pintype "passive"))
      (node (ref "J7") (pin "3") (pinfunction "3_3") (pintype "passive"))
      (node (ref "J7") (pin "4") (pinfunction "4_4") (pintype "passive"))
      (node (ref "J7") (pin "5") (pinfunction "5_5") (pintype "passive"))
      (node (ref "J8") (pin "2") (pinfunction "2_2") (pintype "passive"))
      (node (ref "J8") (pin "3") (pinfunction "3_3") (pintype "passive"))
      (node (ref "J8") (pin "4") (pinfunction "4_4") (pintype "passive"))
      (node (ref "J8") (pin "5") (pinfunction "5_5") (pintype "passive"))
      (node (ref "R10") (pin "1") (pinfunction "1_1") (pintype "passive"))
      (node (ref "R11") (pin "1") (pinfunction "1_1") (pintype "passive"))
      (node (ref "R2") (pin "1") (pinfunction "1_1") (pintype "passive"))
      (node (ref "R3") (pin "1") (pinfunction "1_1") (pintype "passive"))
      (node (ref "R4") (pin "1") (pinfunction "1_1") (pintype "passive"))
      (node (ref "R5") (pin "1") (pinfunction "1_1") (pintype "passive"))
      (node (ref "R7") (pin "1") (pinfunction "1_1") (pintype "passive"))
      (node (ref "R8") (pin "1") (pinfunction "1_1") (pintype "passive"))
    )
    (net (code "36") (name "Net-(IC5-START)") (class "Default")
      (node (ref "IC5") (pin "3") (pinfunction "START_3") (pintype "passive"))
      (node (ref "R6") (pin "2") (pinfunction "2_2") (pintype "passive"))
    )
    (net (code "37") (name "Net-(IC5-VREG)") (class "Default")
      (node (ref "C36") (pin "1") (pinfunction "1_1") (pintype "passive"))
      (node (ref "IC5") (pin "13") (pinfunction "VREG_13") (pintype "passive"))
    )
    (net (code "38") (name "Net-(IC6-START)") (class "Default")
      (node (ref "IC6") (pin "3") (pinfunction "START_3") (pintype "passive"))
      (node (ref "R9") (pin "2") (pinfunction "2_2") (pintype "passive"))
    )
    (net (code "39") (name "Net-(IC6-VREG)") (class "Default")
      (node (ref "C39") (pin "1") (pinfunction "1_1") (pintype "passive"))
      (node (ref "IC6") (pin "13") (pinfunction "VREG_13") (pintype "passive"))
    )
    (net (code "40") (name "OUT_MAIN_HV_DUAL_A") (class "Default")
      (node (ref "R13") (pin "2") (pinfunction "2_2") (pintype "passive"))
    )
    (net (code "41") (name "OUT_SMALL_HV_DUAL_A") (class "Default")
      (node (ref "R15") (pin "2") (pinfunction "2_2") (pintype "passive"))
    )
    (net (code "42") (name "RST_PK_TEST_18") (class "Default")
      (node (ref "DUT_A") (pin "38") (pinfunction "RST_PK_38") (pintype "input"))
    )
    (net (code "43") (name "RSTb_RETIME_18") (class "Default")
      (node (ref "IC10") (pin "6") (pinfunction "~{CLR}_6") (pintype "passive"))
      (node (ref "IC11") (pin "6") (pinfunction "~{CLR}_6") (pintype "passive"))
      (node (ref "IC12") (pin "6") (pinfunction "~{CLR}_6") (pintype "passive"))
      (node (ref "IC13") (pin "6") (pinfunction "~{CLR}_6") (pintype "passive"))
      (node (ref "IC7") (pin "6") (pinfunction "~{CLR}_6") (pintype "passive"))
      (node (ref "IC9") (pin "6") (pinfunction "~{CLR}_6") (pintype "passive"))
    )
    (net (code "44") (name "SCAN_CLK_A_18") (class "Default")
      (node (ref "DUT_A") (pin "56") (pinfunction "SCAN_CLK_56") (pintype "input"))
    )
    (net (code "45") (name "SCAN_INb_18") (class "Default")
      (node (ref "DUT_A") (pin "43") (pinfunction "SCAN_INb_43") (pintype "input"))
    )
    (net (code "46") (name "SCAN_LOADb_A_18") (class "Default")
      (node (ref "DUT_A") (pin "44") (pinfunction "SCAN_LOADb_44") (pintype "input"))
    )
    (net (code "47") (name "SCAN_OUTb_A_18") (class "Default")
      (node (ref "DUT_A") (pin "1") (pinfunction "SCAN_OUTb_1") (pintype "output"))
    )
    (net (code "48") (name "SPI_CLK_MAIN_SINGLE_A_33") (class "Default")
      (node (ref "IC5") (pin "12") (pinfunction "SCLK_12") (pintype "passive"))
    )
    (net (code "49") (name "SPI_CLK_SMALL_SINGLE_A_33") (class "Default")
      (node (ref "IC6") (pin "12") (pinfunction "SCLK_12") (pintype "passive"))
    )
    (net (code "50") (name "SPI_CSb_MAIN_SINGLE_A_33") (class "Default")
      (node (ref "IC5") (pin "11") (pinfunction "CSB_11") (pintype "passive"))
    )
    (net (code "51") (name "SPI_CSb_SMALL_SINGLE_A_33") (class "Default")
      (node (ref "IC6") (pin "11") (pinfunction "CSB_11") (pintype "passive"))
    )
    (net (code "52") (name "SPI_DIN_33") (class "Default")
      (node (ref "IC5") (pin "10") (pinfunction "DIN_10") (pintype "passive"))
      (node (ref "IC6") (pin "10") (pinfunction "DIN_10") (pintype "passive"))
      (node (ref "P32") (pin "1") (pinfunction "1_1") (pintype "passive"))
      (node (ref "P34") (pin "1") (pinfunction "1_1") (pintype "passive"))
    )
    (net (code "53") (name "SPI_DOUT_MAIN_SINGLE_A_33") (class "Default")
      (node (ref "IC5") (pin "9") (pinfunction "DOUT_9") (pintype "passive"))
    )
    (net (code "54") (name "SPI_DOUT_SMALL_SINGLE_A_33") (class "Default")
      (node (ref "IC6") (pin "9") (pinfunction "DOUT_9") (pintype "passive"))
    )
    (net (code "55") (name "TDC_CLK") (class "Default")
      (node (ref "IC5") (pin "5") (pinfunction "CLOCK_5") (pintype "passive"))
      (node (ref "IC6") (pin "5") (pinfunction "CLOCK_5") (pintype "passive"))
      (node (ref "P31") (pin "1") (pinfunction "1_1") (pintype "passive"))
      (node (ref "P33") (pin "1") (pinfunction "1_1") (pintype "passive"))
    )
    (net (code "56") (name "TDC_EN_MAIN_SINGLE_A_33") (class "Default")
      (node (ref "IC5") (pin "1") (pinfunction "ENABLE_1") (pintype "passive"))
    )
    (net (code "57") (name "TDC_EN_SMALL_SINGLE_A_33") (class "Default")
      (node (ref "IC6") (pin "1") (pinfunction "ENABLE_1") (pintype "passive"))
    )
    (net (code "58") (name "TDC_INTRb_MAIN_SINGLE_A_33") (class "Default")
      (node (ref "IC5") (pin "8") (pinfunction "INTB_8") (pintype "passive"))
    )
    (net (code "59") (name "TDC_INTRb_SMALL_SINGLE_A_33") (class "Default")
      (node (ref "IC6") (pin "8") (pinfunction "INTB_8") (pintype "passive"))
    )
    (net (code "60") (name "TDC_TRIGG_MAIN_SINGLE_A_33") (class "Default")
      (node (ref "IC5") (pin "2") (pinfunction "TRIGG_2") (pintype "passive"))
    )
    (net (code "61") (name "TDC_TRIGG_SMALL_SINGLE_A_33") (class "Default")
      (node (ref "IC6") (pin "2") (pinfunction "TRIGG_2") (pintype "passive"))
    )
    (net (code "62") (name "VBG_TEST_A") (class "Default")
      (node (ref "C58") (pin "2") (pinfunction "2_2") (pintype "passive"))
      (node (ref "DUT_A") (pin "49") (pinfunction "VBG_49") (pintype "output"))
    )
    (net (code "63") (name "VDAC_MAIN_A") (class "Default")
      (node (ref "C60") (pin "2") (pinfunction "2_2") (pintype "passive"))
      (node (ref "DUT_A") (pin "30") (pinfunction "VDAC_MAIN_30") (pintype "bidirectional"))
    )
    (net (code "64") (name "VDAC_SMALL_A") (class "Default")
      (node (ref "C59") (pin "2") (pinfunction "2_2") (pintype "passive"))
      (node (ref "DUT_A") (pin "32") (pinfunction "VDAC_SMALL_32") (pintype "bidirectional"))
    )
    (net (code "65") (name "VDDAON_A") (class "Default")
      (node (ref "C48") (pin "2") (pinfunction "2_2") (pintype "passive"))
      (node (ref "C49") (pin "2") (pinfunction "2_2") (pintype "passive"))
      (node (ref "C50") (pin "2") (pinfunction "2_2") (pintype "passive"))
      (node (ref "C51") (pin "2") (pinfunction "2_2") (pintype "passive"))
      (node (ref "DUT_A") (pin "25") (pinfunction "VDDAON_25") (pintype "power_in"))
      (node (ref "DUT_A") (pin "34") (pinfunction "VDDAON_34") (pintype "power_in"))
      (node (ref "DUT_A") (pin "40") (pinfunction "VDDAON_40") (pintype "power_in"))
      (node (ref "DUT_A") (pin "46") (pinfunction "VDDAON_46") (pintype "power_in"))
    )
    (net (code "66") (name "VDDHV") (class "Default")
      (node (ref "C54") (pin "2") (pinfunction "2_2") (pintype "passive"))
      (node (ref "C55") (pin "2") (pinfunction "2_2") (pintype "passive"))
      (node (ref "C56") (pin "2") (pinfunction "2_2") (pintype "passive"))
      (node (ref "DUT_A") (pin "26") (pinfunction "VDDHV_26") (pintype "power_in"))
      (node (ref "DUT_A") (pin "36") (pinfunction "VDDHV_36") (pintype "power_in"))
      (node (ref "DUT_A") (pin "45") (pinfunction "VDDHV_45") (pintype "power_in"))
    )
    (net (code "67") (name "VDDMAIN_A") (class "Default")
      (node (ref "C52") (pin "2") (pinfunction "2_2") (pintype "passive"))
      (node (ref "DUT_A") (pin "13") (pinfunction "VDDMAIN_13") (pintype "power_in"))
    )
    (net (code "68") (name "VDDSMALL_A") (class "Default")
      (node (ref "C57") (pin "2") (pinfunction "2_2") (pintype "passive"))
      (node (ref "DUT_A") (pin "10") (pinfunction "VDDSMALL_10") (pintype "power_in"))
    )
    (net (code "69") (name "VDDTEST") (class "Default")
      (node (ref "DUT_A") (pin "51") (pinfunction "VDDTEST_51") (pintype "power_in"))
    )
    (net (code "70") (name "VOUT_PK_TEST_A") (class "Default")
      (node (ref "DUT_A") (pin "50") (pinfunction "VOUT_PK_50") (pintype "output"))
    )
    (net (code "71") (name "VREF_ATTEN_MAIN_A") (class "Default")
      (node (ref "C62") (pin "2") (pinfunction "2_2") (pintype "passive"))
      (node (ref "DUT_A") (pin "23") (pinfunction "VREF_ATTEN_MAIN_23") (pintype "input"))
    )
    (net (code "72") (name "VREF_PREAMP_A") (class "Default")
      (node (ref "C61") (pin "2") (pinfunction "2_2") (pintype "passive"))
      (node (ref "DUT_A") (pin "29") (pinfunction "VREF_PREAMP_29") (pintype "bidirectional"))
    )
    (net (code "73") (name "VRST_PK_TEST_A") (class "Default")
      (node (ref "DUT_A") (pin "55") (pinfunction "VRST_PK_TEST_55") (pintype "input"))
    )
    (net (code "74") (name "unconnected-(DUT_A-NC-Pad16)") (class "Default")
      (node (ref "DUT_A") (pin "16") (pinfunction "NC_16") (pintype "passive"))
    )
    (net (code "75") (name "unconnected-(DUT_A-NC-Pad19)") (class "Default")
      (node (ref "DUT_A") (pin "19") (pinfunction "NC_19") (pintype "passive"))
    )
    (net (code "76") (name "unconnected-(DUT_A-NC-Pad21)") (class "Default")
      (node (ref "DUT_A") (pin "21") (pinfunction "NC_21") (pintype "passive"))
    )
    (net (code "77") (name "unconnected-(DUT_A-NC-Pad24)") (class "Default")
      (node (ref "DUT_A") (pin "24") (pinfunction "NC_24") (pintype "passive"))
    )
    (net (code "78") (name "unconnected-(DUT_A-NC-Pad27)") (class "Default")
      (node (ref "DUT_A") (pin "27") (pinfunction "NC_27") (pintype "passive"))
    )
    (net (code "79") (name "unconnected-(DUT_A-NC-Pad31)") (class "Default")
      (node (ref "DUT_A") (pin "31") (pinfunction "NC_31") (pintype "passive"))
    )
    (net (code "80") (name "unconnected-(DUT_A-NC-Pad33)") (class "Default")
      (node (ref "DUT_A") (pin "33") (pinfunction "NC_33") (pintype "passive"))
    )
    (net (code "81") (name "unconnected-(DUT_A-NC-Pad37)") (class "Default")
      (node (ref "DUT_A") (pin "37") (pinfunction "NC_37") (pintype "passive"))
    )
    (net (code "82") (name "unconnected-(DUT_A-NC-Pad39)") (class "Default")
      (node (ref "DUT_A") (pin "39") (pinfunction "NC_39") (pintype "passive"))
    )
    (net (code "83") (name "unconnected-(DUT_A-NC-Pad42)") (class "Default")
      (node (ref "DUT_A") (pin "42") (pinfunction "NC_42") (pintype "passive"))
    )
    (net (code "84") (name "unconnected-(DUT_A-NC-Pad48)") (class "Default")
      (node (ref "DUT_A") (pin "48") (pinfunction "NC_48") (pintype "passive"))
    )
    (net (code "85") (name "unconnected-(IC5-NC-Pad6)") (class "Default")
      (node (ref "IC5") (pin "6") (pinfunction "NC_6") (pintype "passive"))
    )
    (net (code "86") (name "unconnected-(IC6-NC-Pad6)") (class "Default")
      (node (ref "IC6") (pin "6") (pinfunction "NC_6") (pintype "passive"))
    )
    (net (code "87") (name "unconnected-(IC7-~{Q}-Pad3)") (class "Default")
      (node (ref "IC7") (pin "3") (pinfunction "~{Q}_3") (pintype "passive"))
    )
    (net (code "88") (name "unconnected-(IC9-~{Q}-Pad3)") (class "Default")
      (node (ref "IC9") (pin "3") (pinfunction "~{Q}_3") (pintype "passive"))
    )
    (net (code "89") (name "unconnected-(IC10-~{Q}-Pad3)") (class "Default")
      (node (ref "IC10") (pin "3") (pinfunction "~{Q}_3") (pintype "passive"))
    )
    (net (code "90") (name "unconnected-(IC11-~{Q}-Pad3)") (class "Default")
      (node (ref "IC11") (pin "3") (pinfunction "~{Q}_3") (pintype "passive"))
    )
    (net (code "91") (name "unconnected-(IC12-~{Q}-Pad3)") (class "Default")
      (node (ref "IC12") (pin "3") (pinfunction "~{Q}_3") (pintype "passive"))
    )
    (net (code "92") (name "unconnected-(IC13-~{Q}-Pad3)") (class "Default")
      (node (ref "IC13") (pin "3") (pinfunction "~{Q}_3") (pintype "passive"))
    )
  )
)
